# Arduino__Connectors.net
KiCad netlist of a schematic drawn in Altium Designer
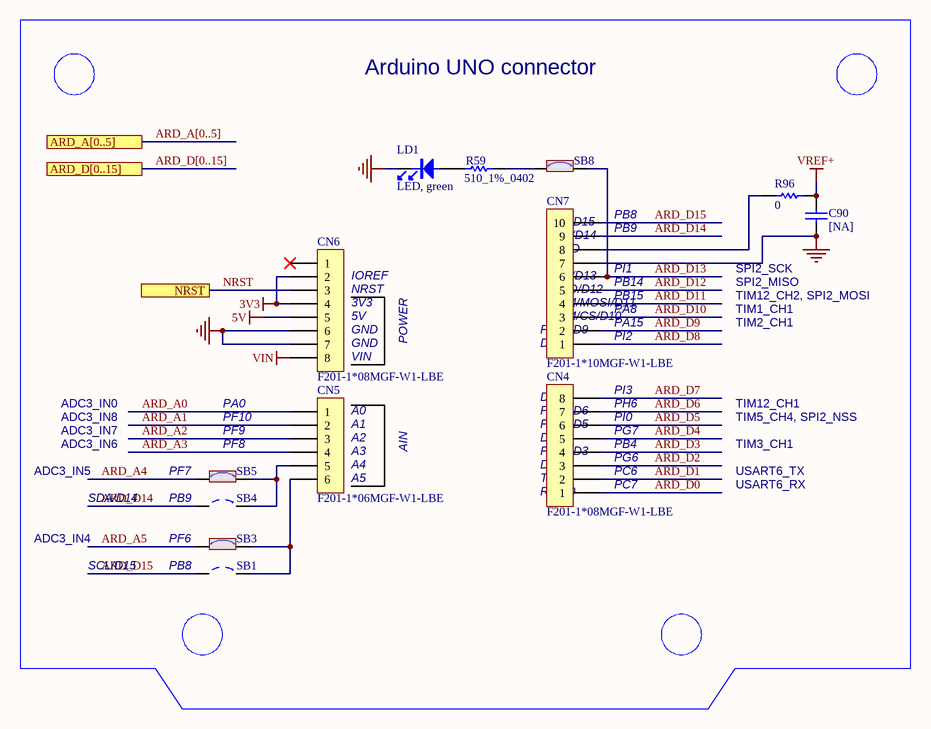
[diagram p0: Arduino_ Connectors.SchDoc]

(export (version "E")
  (design (tool "Eeschema 10.0.6"))
  (components
    (comp (ref "C90")
      (value "[NA]")
      (footprint "0402C")
      (description "Capacitor,NA,0402")
      (libsource (lib "MCD_TOOLS") (part "Cap_NA_0402"))
    )
    (comp (ref "CN4")
      (value "F201-1*08MGF-W1-LBE")
      (footprint "F201-1*08MGF-W1-BA")
      (description "Header, 8-Pins, Single row, female SMD")
      (libsource (lib "MCD_TOOLS") (part "F201-1*08MGF-W1-BA"))
    )
    (comp (ref "CN5")
      (value "F201-1*06MGF-W1-LBE")
      (footprint "F201-1*06MGF-W1-BA")
      (description "Header, 6-Pins, Single row, female SMD")
      (libsource (lib "MCD_TOOLS") (part "F201-1*06MGF-W1-BA"))
    )
    (comp (ref "CN6")
      (value "F201-1*08MGF-W1-LBE")
      (footprint "F201-1*08MGF-W1-BA")
      (description "Header, 8-Pins, Single row, female SMD")
      (libsource (lib "") (part "F201-1*08MGF-W1-BA_1"))
    )
    (comp (ref "CN7")
      (value "F201-1*10MGF-W1-LBE")
      (footprint "F201-1*10MGF-W1-BA")
      (description "Header, 10-Pins, Single row, female SMD")
      (libsource (lib "MCD_TOOLS") (part "F201-1*10MGF-W1-BA"))
    )
    (comp (ref "LD1")
      (value "LED, green")
      (footprint "0603D")
      (description "LED, green, 0603")
      (libsource (lib "MCD_TOOLS") (part "LED_green"))
    )
    (comp (ref "R59")
      (value "510_1%_0402")
      (footprint "0402R")
      (description "Resistor,510,0402,1%,YAGEO")
      (libsource (lib "MCD_TOOLS") (part "Res_510_1%_0402"))
    )
    (comp (ref "R96")
      (value "0")
      (footprint "0402R")
      (description "Resistor,0,0402,5%,YAGEO")
      (libsource (lib "MCD_TOOLS") (part "Res_0_5%_0402"))
    )
    (comp (ref "SB1")
      (value "Solder Bridge OFF")
      (footprint "JP2_SMD")
      (libsource (lib "MCD_TOOLS") (part "SB_OFF"))
    )
    (comp (ref "SB3")
      (value "Solder Bridge ON")
      (footprint "JP2_SMD")
      (libsource (lib "MCD_TOOLS") (part "SB_ON"))
    )
    (comp (ref "SB4")
      (value "Solder Bridge OFF")
      (footprint "JP2_SMD")
      (libsource (lib "MCD_TOOLS") (part "SB_OFF"))
    )
    (comp (ref "SB5")
      (value "Solder Bridge ON")
      (footprint "JP2_SMD")
      (libsource (lib "MCD_TOOLS") (part "SB_ON"))
    )
    (comp (ref "SB8")
      (value "Solder Bridge ON")
      (footprint "JP2_SMD")
      (libsource (lib "MCD_TOOLS") (part "SB_ON"))
    )
  )
  (nets
    (net (code "1") (name "/ARD_A0") (class "Default")
      (node (ref "CN5") (pin "1") (pinfunction "1_1") (pintype "passive"))
    )
    (net (code "2") (name "/ARD_A1") (class "Default")
      (node (ref "CN5") (pin "2") (pinfunction "2_2") (pintype "passive"))
    )
    (net (code "3") (name "/ARD_A2") (class "Default")
      (node (ref "CN5") (pin "3") (pinfunction "3_3") (pintype "passive"))
    )
    (net (code "4") (name "/ARD_A3") (class "Default")
      (node (ref "CN5") (pin "4") (pinfunction "4_4") (pintype "passive"))
    )
    (net (code "5") (name "/ARD_A4") (class "Default")
      (node (ref "SB5") (pin "1") (pinfunction "1_1") (pintype "passive"))
    )
    (net (code "6") (name "/ARD_A5") (class "Default")
      (node (ref "SB3") (pin "1") (pinfunction "1_1") (pintype "passive"))
    )
    (net (code "8") (name "/ARD_D0") (class "Default")
      (node (ref "CN4") (pin "1") (pinfunction "1_1") (pintype "passive"))
    )
    (net (code "9") (name "/ARD_D1") (class "Default")
      (node (ref "CN4") (pin "2") (pinfunction "2_2") (pintype "passive"))
    )
    (net (code "10") (name "/ARD_D2") (class "Default")
      (node (ref "CN4") (pin "3") (pinfunction "3_3") (pintype "passive"))
    )
    (net (code "11") (name "/ARD_D3") (class "Default")
      (node (ref "CN4") (pin "4") (pinfunction "4_4") (pintype "passive"))
    )
    (net (code "12") (name "/ARD_D4") (class "Default")
      (node (ref "CN4") (pin "5") (pinfunction "5_5") (pintype "passive"))
    )
    (net (code "13") (name "/ARD_D5") (class "Default")
      (node (ref "CN4") (pin "6") (pinfunction "6_6") (pintype "passive"))
    )
    (net (code "14") (name "/ARD_D6") (class "Default")
      (node (ref "CN4") (pin "7") (pinfunction "7_7") (pintype "passive"))
    )
    (net (code "15") (name "/ARD_D7") (class "Default")
      (node (ref "CN4") (pin "8") (pinfunction "8_8") (pintype "passive"))
    )
    (net (code "16") (name "/ARD_D8") (class "Default")
      (node (ref "CN7") (pin "1") (pinfunction "1_1") (pintype "passive"))
    )
    (net (code "17") (name "/ARD_D9") (class "Default")
      (node (ref "CN7") (pin "2") (pinfunction "2_2") (pintype "passive"))
    )
    (net (code "18") (name "/ARD_D10") (class "Default")
      (node (ref "CN7") (pin "3") (pinfunction "3_3") (pintype "passive"))
    )
    (net (code "19") (name "/ARD_D11") (class "Default")
      (node (ref "CN7") (pin "4") (pinfunction "4_4") (pintype "passive"))
    )
    (net (code "20") (name "/ARD_D12") (class "Default")
      (node (ref "CN7") (pin "5") (pinfunction "5_5") (pintype "passive"))
    )
    (net (code "21") (name "/ARD_D13") (class "Default")
      (node (ref "CN7") (pin "6") (pinfunction "6_6") (pintype "passive"))
      (node (ref "SB8") (pin "2") (pinfunction "2_2") (pintype "passive"))
    )
    (net (code "22") (name "/ARD_D14") (class "Default")
      (node (ref "CN7") (pin "9") (pinfunction "9_9") (pintype "passive"))
      (node (ref "SB4") (pin "1") (pinfunction "1_1") (pintype "passive"))
    )
    (net (code "23") (name "/ARD_D15") (class "Default")
      (node (ref "CN7") (pin "10") (pinfunction "10_10") (pintype "passive"))
      (node (ref "SB1") (pin "1") (pinfunction "1_1") (pintype "passive"))
    )
    (net (code "25") (name "/NRST") (class "Default")
      (node (ref "CN6") (pin "3") (pinfunction "3_3") (pintype "passive"))
    )
    (net (code "26") (name "3V3") (class "Default")
      (node (ref "CN6") (pin "2") (pinfunction "2_2") (pintype "passive"))
      (node (ref "CN6") (pin "4") (pinfunction "4_4") (pintype "passive"))
    )
    (net (code "27") (name "5V") (class "Default")
      (node (ref "CN6") (pin "5") (pinfunction "5_5") (pintype "passive"))
    )
    (net (code "28") (name "GND") (class "Default")
      (node (ref "C90") (pin "1") (pinfunction "1_1") (pintype "passive"))
      (node (ref "CN6") (pin "6") (pinfunction "6_6") (pintype "passive"))
      (node (ref "CN6") (pin "7") (pinfunction "7_7") (pintype "passive"))
      (node (ref "CN7") (pin "7") (pinfunction "7_7") (pintype "passive"))
      (node (ref "LD1") (pin "2") (pintype "passive"))
    )
    (net (code "29") (name "Net-(CN5-Pad5)") (class "Default")
      (node (ref "CN5") (pin "5") (pinfunction "5_5") (pintype "passive"))
      (node (ref "SB4") (pin "2") (pinfunction "2_2") (pintype "passive"))
      (node (ref "SB5") (pin "2") (pinfunction "2_2") (pintype "passive"))
    )
    (net (code "30") (name "Net-(CN5-Pad6)") (class "Default")
      (node (ref "CN5") (pin "6") (pinfunction "6_6") (pintype "passive"))
      (node (ref "SB1") (pin "2") (pinfunction "2_2") (pintype "passive"))
      (node (ref "SB3") (pin "2") (pinfunction "2_2") (pintype "passive"))
    )
    (net (code "31") (name "Net-(CN7-Pad8)") (class "Default")
      (node (ref "CN7") (pin "8") (pinfunction "8_8") (pintype "passive"))
      (node (ref "R96") (pin "1") (pinfunction "1_1") (pintype "passive"))
    )
    (net (code "32") (name "Net-(LD1-Pad1)") (class "Default")
      (node (ref "LD1") (pin "1") (pintype "passive"))
      (node (ref "R59") (pin "1") (pinfunction "1_1") (pintype "passive"))
    )
    (net (code "33") (name "Net-(R59-Pad2)") (class "Default")
      (node (ref "R59") (pin "2") (pinfunction "2_2") (pintype "passive"))
      (node (ref "SB8") (pin "1") (pinfunction "1_1") (pintype "passive"))
    )
    (net (code "34") (name "VIN") (class "Default")
      (node (ref "CN6") (pin "8") (pinfunction "8_8") (pintype "passive"))
    )
    (net (code "35") (name "VREF+") (class "Default")
      (node (ref "C90") (pin "2") (pinfunction "2_2") (pintype "passive"))
      (node (ref "R96") (pin "2") (pinfunction "2_2") (pintype "passive"))
    )
    (net (code "36") (name "unconnected-(CN6-Pad1)") (class "Default")
      (node (ref "CN6") (pin "1") (pinfunction "1_1") (pintype "passive+no_connect"))
    )
  )
)
